# dlock13.net
KiCad netlist of a schematic drawn in EAGLE
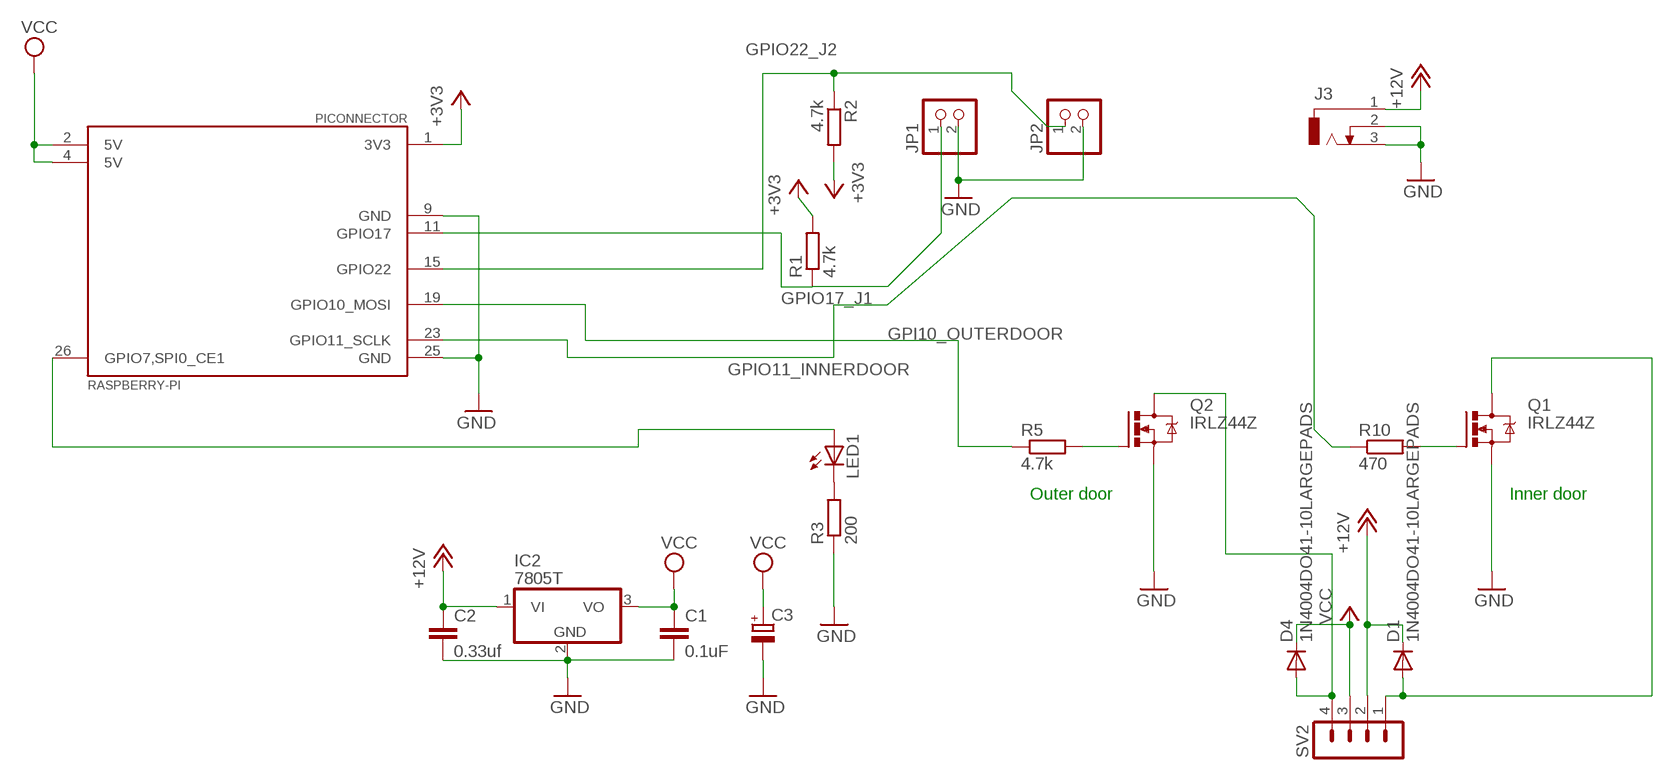
[diagram p0: schematic, sheet 1]

(export (version "E")
  (design (tool "Eeschema 10.0.6"))
  (components
    (comp (ref "C1")
      (value "0.1uF")
      (footprint "eagle-import:C2.5-3")
      (libsource (lib "eagle-import") (part "CC2.5-3LARGEPADS"))
    )
    (comp (ref "C2")
      (value "0.33uf")
      (footprint "eagle-import:C2.5-3")
      (libsource (lib "eagle-import") (part "CC2.5-3LARGEPADS"))
    )
    (comp (ref "C3")
      (value "CPOL-EUE1,8-4LARGEPADS")
      (footprint "eagle-import:E1,8-4")
      (libsource (lib "eagle-import") (part "CPOL-EUE1,8-4LARGEPADS"))
    )
    (comp (ref "D1")
      (value "1N4004DO41-10LARGEPADS")
      (footprint "eagle-import:DO41-10")
      (libsource (lib "eagle-import") (part "1N4004DO41-10LARGEPADS"))
    )
    (comp (ref "D4")
      (value "1N4004DO41-10LARGEPADS")
      (footprint "eagle-import:DO41-10")
      (libsource (lib "eagle-import") (part "1N4004DO41-10LARGEPADS"))
    )
    (comp (ref "IC2")
      (value "7805T")
      (footprint "eagle-import:TO220H")
      (libsource (lib "eagle-import") (part "78T05"))
    )
    (comp (ref "J3")
      (value "DCJ0303DCJ0303LARGEPADS")
      (footprint "eagle-import:DCJ0303")
      (libsource (lib "eagle-import") (part "DCJ0303DCJ0303LARGEPADS"))
    )
    (comp (ref "JP1")
      (value "PINHD-1X2")
      (footprint "eagle-import:1X02")
      (libsource (lib "eagle-import") (part "PINHD-1X2"))
    )
    (comp (ref "JP2")
      (value "PINHD-1X21X02LARGEPADS")
      (footprint "eagle-import:1X02")
      (libsource (lib "eagle-import") (part "PINHD-1X21X02LARGEPADS"))
    )
    (comp (ref "LED1")
      (value "LEDLED5MMLARGEPADS")
      (footprint "eagle-import:LED5MM")
      (libsource (lib "eagle-import") (part "LEDLED5MMLARGEPADS"))
    )
    (comp (ref "PICONNECTOR")
      (value "RASPBERRY-PI")
      (footprint "eagle-import:RASPBERRY-PI_REV1")
      (libsource (lib "eagle-import") (part "RASPBERRY-PI_REV1PIWITHPADSREMOVED"))
    )
    (comp (ref "Q1")
      (value "IRLZ44Z")
      (footprint "eagle-import:TO220BH")
      (libsource (lib "eagle-import") (part "IRLZ44Z"))
    )
    (comp (ref "Q2")
      (value "IRLZ44Z")
      (footprint "eagle-import:TO220BH")
      (libsource (lib "eagle-import") (part "IRLZ44Z"))
    )
    (comp (ref "R1")
      (value "4.7k")
      (footprint "eagle-import:0207_10")
      (libsource (lib "eagle-import") (part "R-EU_0207/10LARGEPADS"))
    )
    (comp (ref "R2")
      (value "4.7k")
      (footprint "eagle-import:0207_10")
      (libsource (lib "eagle-import") (part "R-EU_0207/10LARGEPADS"))
    )
    (comp (ref "R3")
      (value "200")
      (footprint "eagle-import:0207_10")
      (libsource (lib "eagle-import") (part "R-EU_0207/10LARGEPADS"))
    )
    (comp (ref "R5")
      (value "4.7k")
      (footprint "eagle-import:0207_10")
      (libsource (lib "eagle-import") (part "R-EU_0207/10LARGEPADS"))
    )
    (comp (ref "R10")
      (value "470")
      (footprint "eagle-import:0207_10")
      (libsource (lib "eagle-import") (part "R-EU_0207/10LARGEPADS"))
    )
    (comp (ref "SV2")
      (value "MA04-1MA04-1LARGEPADS")
      (footprint "eagle-import:MA04-1")
      (libsource (lib "eagle-import") (part "MA04-1MA04-1LARGEPADS"))
    )
  )
  (nets
    (net (code "1") (name "+3V3") (class "Default")
      (node (ref "PICONNECTOR") (pin "1") (pinfunction "3V3_1") (pintype "bidirectional"))
      (node (ref "R1") (pin "2") (pinfunction "2_2") (pintype "passive"))
      (node (ref "R2") (pin "2") (pinfunction "2_2") (pintype "passive"))
    )
    (net (code "2") (name "+12V") (class "Default")
      (node (ref "C2") (pin "1") (pinfunction "1_1") (pintype "passive"))
      (node (ref "D1") (pin "C") (pinfunction "C_C") (pintype "passive"))
      (node (ref "IC2") (pin "1") (pinfunction "VI_1") (pintype "input"))
      (node (ref "J3") (pin "1") (pinfunction "1_1") (pintype "passive"))
      (node (ref "SV2") (pin "2") (pinfunction "2_2") (pintype "passive"))
    )
    (net (code "3") (name "/GPI10_OUTERDOOR") (class "Default")
      (node (ref "PICONNECTOR") (pin "19") (pinfunction "GPIO10_MOSI_19") (pintype "bidirectional"))
      (node (ref "R5") (pin "1") (pinfunction "1_1") (pintype "passive"))
    )
    (net (code "4") (name "/GPIO11_INNERDOOR") (class "Default")
      (node (ref "PICONNECTOR") (pin "23") (pinfunction "GPIO11_SCLK_23") (pintype "bidirectional"))
      (node (ref "R10") (pin "1") (pinfunction "1_1") (pintype "passive"))
    )
    (net (code "5") (name "/GPIO17_J1") (class "Default")
      (node (ref "JP1") (pin "1") (pinfunction "1_1") (pintype "passive"))
      (node (ref "PICONNECTOR") (pin "11") (pinfunction "GPIO17_11") (pintype "bidirectional"))
      (node (ref "R1") (pin "1") (pinfunction "1_1") (pintype "passive"))
    )
    (net (code "6") (name "/GPIO22_J2") (class "Default")
      (node (ref "JP2") (pin "1") (pinfunction "1_1") (pintype "passive"))
      (node (ref "PICONNECTOR") (pin "15") (pinfunction "GPIO22_15") (pintype "bidirectional"))
      (node (ref "R2") (pin "1") (pinfunction "1_1") (pintype "passive"))
    )
    (net (code "7") (name "GND") (class "Default")
      (node (ref "C1") (pin "2") (pinfunction "2_2") (pintype "passive"))
      (node (ref "C2") (pin "2") (pinfunction "2_2") (pintype "passive"))
      (node (ref "C3") (pin "-") (pinfunction "-_-") (pintype "passive"))
      (node (ref "IC2") (pin "2") (pinfunction "GND_2") (pintype "passive"))
      (node (ref "J3") (pin "2") (pinfunction "2_2") (pintype "passive"))
      (node (ref "J3") (pin "3") (pinfunction "3_3") (pintype "passive"))
      (node (ref "JP1") (pin "2") (pinfunction "2_2") (pintype "passive"))
      (node (ref "JP2") (pin "2") (pinfunction "2_2") (pintype "passive"))
      (node (ref "PICONNECTOR") (pin "25") (pinfunction "GND_25") (pintype "bidirectional"))
      (node (ref "PICONNECTOR") (pin "9") (pinfunction "GND_9") (pintype "bidirectional"))
      (node (ref "Q1") (pin "S") (pinfunction "S_S") (pintype "passive"))
      (node (ref "Q2") (pin "S") (pinfunction "S_S") (pintype "passive"))
      (node (ref "R3") (pin "1") (pinfunction "1_1") (pintype "passive"))
    )
    (net (code "8") (name "Net-(D1-PadA)") (class "Default")
      (node (ref "D1") (pin "A") (pinfunction "A_A") (pintype "passive"))
      (node (ref "Q1") (pin "D") (pinfunction "D_D") (pintype "passive"))
      (node (ref "SV2") (pin "1") (pinfunction "1_1") (pintype "passive"))
    )
    (net (code "9") (name "Net-(D4-PadA)") (class "Default")
      (node (ref "D4") (pin "A") (pinfunction "A_A") (pintype "passive"))
      (node (ref "Q2") (pin "D") (pinfunction "D_D") (pintype "passive"))
      (node (ref "SV2") (pin "4") (pinfunction "4_4") (pintype "passive"))
    )
    (net (code "10") (name "Net-(LED1-C)") (class "Default")
      (node (ref "LED1") (pin "K") (pinfunction "C_K") (pintype "passive"))
      (node (ref "R3") (pin "2") (pinfunction "2_2") (pintype "passive"))
    )
    (net (code "11") (name "Net-(PICONNECTOR-GPIO7,SPI0_CE1)") (class "Default")
      (node (ref "LED1") (pin "A") (pinfunction "A_A") (pintype "passive"))
      (node (ref "PICONNECTOR") (pin "26") (pinfunction "GPIO7,SPI0_CE1_26") (pintype "bidirectional"))
    )
    (net (code "12") (name "Net-(Q1-PadG)") (class "Default")
      (node (ref "Q1") (pin "G") (pinfunction "G_G") (pintype "passive"))
      (node (ref "R10") (pin "2") (pinfunction "2_2") (pintype "passive"))
    )
    (net (code "13") (name "Net-(Q2-PadG)") (class "Default")
      (node (ref "Q2") (pin "G") (pinfunction "G_G") (pintype "passive"))
      (node (ref "R5") (pin "2") (pinfunction "2_2") (pintype "passive"))
    )
    (net (code "14") (name "VCC") (class "Default")
      (node (ref "C1") (pin "1") (pinfunction "1_1") (pintype "passive"))
      (node (ref "C3") (pin "+") (pinfunction "+_+") (pintype "passive"))
      (node (ref "D4") (pin "C") (pinfunction "C_C") (pintype "passive"))
      (node (ref "IC2") (pin "3") (pinfunction "VO_3") (pintype "passive"))
      (node (ref "PICONNECTOR") (pin "2") (pinfunction "5V_2") (pintype "bidirectional"))
      (node (ref "PICONNECTOR") (pin "4") (pinfunction "5V_4") (pintype "bidirectional"))
      (node (ref "SV2") (pin "3") (pinfunction "3_3") (pintype "passive"))
    )
  )
)
